# CLONE_EEPROM_95040_GMC_2A.net
KiCad netlist of a schematic drawn in EAGLE
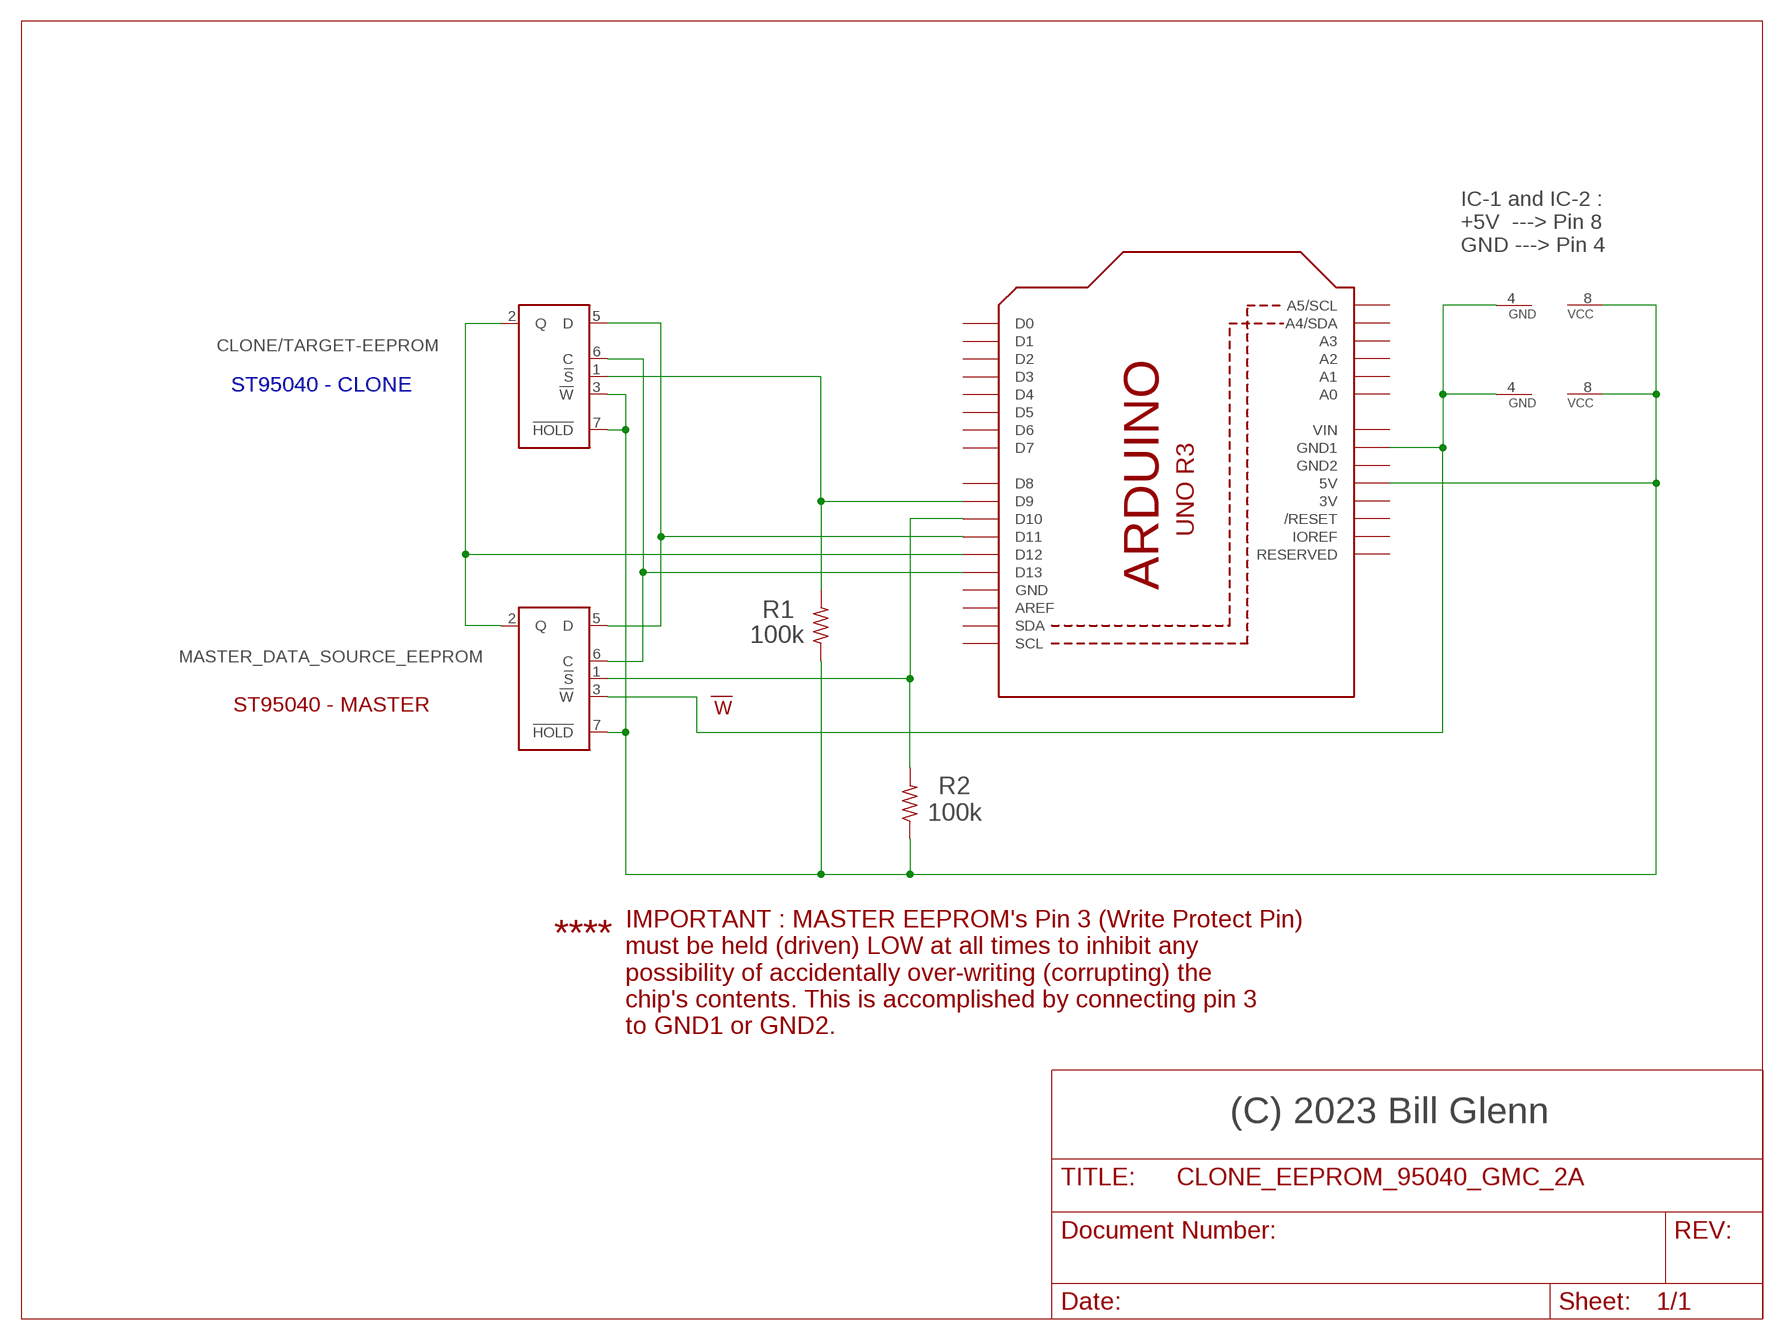
[diagram p0: schematic, sheet 1]

(export (version "E")
  (design (tool "Eeschema 10.0.6"))
  (components
    (comp (ref "CLONE/TARGET-EEPROM")
      (value "ST95040 - CLONE")
      (footprint "eagle-import:DIL-08")
      (libsource (lib "eagle-import") (part "ST95P08B"))
    )
    (comp (ref "MASTER_DATA_SOURCE_EEPROM")
      (value "ST95040 - MASTER")
      (footprint "eagle-import:DIL-08")
      (libsource (lib "eagle-import") (part "ST95P08B"))
    )
    (comp (ref "R1")
      (value "100k")
      (footprint "eagle-import:0207_15")
      (libsource (lib "eagle-import") (part "R-US_0207/15"))
    )
    (comp (ref "R2")
      (value "100k")
      (footprint "eagle-import:0207_15")
      (libsource (lib "eagle-import") (part "R-US_0207/15"))
    )
    (comp (ref "U1")
      (value "ARDUINOR3-BPLACE")
      (footprint "eagle-import:ARDUINOR3-BPLACE")
      (libsource (lib "eagle-import") (part "ARDUINOR3-BPLACE"))
    )
  )
  (nets
    (net (code "1") (name "/3V") (class "Default")
      (node (ref "U1") (pin "3V") (pinfunction "3V_3V") (pintype "power_in"))
    )
    (net (code "2") (name "/GND") (class "Default")
      (node (ref "U1") (pin "GND") (pinfunction "GND_GND") (pintype "power_in"))
    )
    (net (code "3") (name "/GND2") (class "Default")
      (node (ref "U1") (pin "GND2") (pinfunction "GND2_GND2") (pintype "power_in"))
    )
    (net (code "4") (name "/VIN") (class "Default")
      (node (ref "U1") (pin "VIN") (pinfunction "VIN_VIN") (pintype "power_in"))
    )
    (net (code "5") (name "Net-(CLONE/TARGET-EEPROMA-C)") (class "Default")
      (node (ref "CLONE/TARGET-EEPROM") (pin "6") (pinfunction "C_6") (pintype "input"))
      (node (ref "MASTER_DATA_SOURCE_EEPROM") (pin "6") (pinfunction "C_6") (pintype "input"))
      (node (ref "U1") (pin "D13") (pinfunction "D13_D13") (pintype "bidirectional"))
    )
    (net (code "6") (name "Net-(CLONE/TARGET-EEPROMA-D)") (class "Default")
      (node (ref "CLONE/TARGET-EEPROM") (pin "5") (pinfunction "D_5") (pintype "input"))
      (node (ref "MASTER_DATA_SOURCE_EEPROM") (pin "5") (pinfunction "D_5") (pintype "input"))
      (node (ref "U1") (pin "D11") (pinfunction "D11_D11") (pintype "bidirectional"))
    )
    (net (code "7") (name "Net-(CLONE/TARGET-EEPROMA-Q)") (class "Default")
      (node (ref "CLONE/TARGET-EEPROM") (pin "2") (pinfunction "Q_2") (pintype "tri_state"))
      (node (ref "MASTER_DATA_SOURCE_EEPROM") (pin "2") (pinfunction "Q_2") (pintype "tri_state"))
      (node (ref "U1") (pin "D12") (pinfunction "D12_D12") (pintype "bidirectional"))
    )
    (net (code "8") (name "Net-(CLONE/TARGET-EEPROMA-~{HOLD})") (class "Default")
      (node (ref "CLONE/TARGET-EEPROM") (pin "3") (pinfunction "~{W}_3") (pintype "input"))
      (node (ref "CLONE/TARGET-EEPROM") (pin "7") (pinfunction "~{HOLD}_7") (pintype "input"))
      (node (ref "CLONE/TARGET-EEPROM") (pin "8") (pinfunction "VCC_8") (pintype "power_in"))
      (node (ref "MASTER_DATA_SOURCE_EEPROM") (pin "7") (pinfunction "~{HOLD}_7") (pintype "input"))
      (node (ref "MASTER_DATA_SOURCE_EEPROM") (pin "8") (pinfunction "VCC_8") (pintype "power_in"))
      (node (ref "R1") (pin "1") (pinfunction "1_1") (pintype "passive"))
      (node (ref "R2") (pin "1") (pinfunction "1_1") (pintype "passive"))
      (node (ref "U1") (pin "5V") (pinfunction "5V_5V") (pintype "power_in"))
    )
    (net (code "9") (name "Net-(CLONE/TARGET-EEPROMA-~{S})") (class "Default")
      (node (ref "CLONE/TARGET-EEPROM") (pin "1") (pinfunction "~{S}_1") (pintype "input"))
      (node (ref "R1") (pin "2") (pinfunction "2_2") (pintype "passive"))
      (node (ref "U1") (pin "D9") (pinfunction "D9_D9") (pintype "bidirectional"))
    )
    (net (code "10") (name "Net-(CLONE/TARGET-EEPROMB-GND)") (class "Default")
      (node (ref "CLONE/TARGET-EEPROM") (pin "4") (pinfunction "GND_4") (pintype "power_in"))
      (node (ref "MASTER_DATA_SOURCE_EEPROM") (pin "3") (pinfunction "~{W}_3") (pintype "input"))
      (node (ref "MASTER_DATA_SOURCE_EEPROM") (pin "4") (pinfunction "GND_4") (pintype "power_in"))
      (node (ref "U1") (pin "GND1") (pinfunction "GND1_GND1") (pintype "power_in"))
    )
    (net (code "11") (name "Net-(MASTER_DATA_SOURCE_EEPROMA-~{S})") (class "Default")
      (node (ref "MASTER_DATA_SOURCE_EEPROM") (pin "1") (pinfunction "~{S}_1") (pintype "input"))
      (node (ref "R2") (pin "2") (pinfunction "2_2") (pintype "passive"))
      (node (ref "U1") (pin "D10") (pinfunction "D10_D10") (pintype "bidirectional"))
    )
    (net (code "12") (name "unconnected-(U1-A4{slash}SDA-PadA4)") (class "Default")
      (node (ref "U1") (pin "A4") (pinfunction "A4/SDA_A4") (pintype "bidirectional"))
    )
    (net (code "13") (name "unconnected-(U1-A5{slash}SCL-PadA5)") (class "Default")
      (node (ref "U1") (pin "A5") (pinfunction "A5/SCL_A5") (pintype "bidirectional"))
    )
    (net (code "14") (name "unconnected-(U1-PadA0)") (class "Default")
      (node (ref "U1") (pin "A0") (pinfunction "A0_A0") (pintype "bidirectional"))
    )
    (net (code "15") (name "unconnected-(U1-PadA1)") (class "Default")
      (node (ref "U1") (pin "A1") (pinfunction "A1_A1") (pintype "bidirectional"))
    )
    (net (code "16") (name "unconnected-(U1-PadA2)") (class "Default")
      (node (ref "U1") (pin "A2") (pinfunction "A2_A2") (pintype "bidirectional"))
    )
    (net (code "17") (name "unconnected-(U1-PadA3)") (class "Default")
      (node (ref "U1") (pin "A3") (pinfunction "A3_A3") (pintype "bidirectional"))
    )
    (net (code "18") (name "unconnected-(U1-PadAREF)") (class "Default")
      (node (ref "U1") (pin "AREF") (pinfunction "AREF_AREF") (pintype "bidirectional"))
    )
    (net (code "19") (name "unconnected-(U1-PadD0)") (class "Default")
      (node (ref "U1") (pin "D0") (pinfunction "D0_D0") (pintype "bidirectional"))
    )
    (net (code "20") (name "unconnected-(U1-PadD1)") (class "Default")
      (node (ref "U1") (pin "D1") (pinfunction "D1_D1") (pintype "bidirectional"))
    )
    (net (code "21") (name "unconnected-(U1-PadD2)") (class "Default")
      (node (ref "U1") (pin "D2") (pinfunction "D2_D2") (pintype "bidirectional"))
    )
    (net (code "22") (name "unconnected-(U1-PadD3)") (class "Default")
      (node (ref "U1") (pin "D3") (pinfunction "D3_D3") (pintype "bidirectional"))
    )
    (net (code "23") (name "unconnected-(U1-PadD4)") (class "Default")
      (node (ref "U1") (pin "D4") (pinfunction "D4_D4") (pintype "bidirectional"))
    )
    (net (code "24") (name "unconnected-(U1-PadD5)") (class "Default")
      (node (ref "U1") (pin "D5") (pinfunction "D5_D5") (pintype "bidirectional"))
    )
    (net (code "25") (name "unconnected-(U1-PadD6)") (class "Default")
      (node (ref "U1") (pin "D6") (pinfunction "D6_D6") (pintype "bidirectional"))
    )
    (net (code "26") (name "unconnected-(U1-PadD7)") (class "Default")
      (node (ref "U1") (pin "D7") (pinfunction "D7_D7") (pintype "bidirectional"))
    )
    (net (code "27") (name "unconnected-(U1-PadD8)") (class "Default")
      (node (ref "U1") (pin "D8") (pinfunction "D8_D8") (pintype "bidirectional"))
    )
    (net (code "28") (name "unconnected-(U1-PadIOREF)") (class "Default")
      (node (ref "U1") (pin "IOREF") (pinfunction "IOREF_IOREF") (pintype "output"))
    )
    (net (code "29") (name "unconnected-(U1-PadRESERVED)") (class "Default")
      (node (ref "U1") (pin "RESERVED") (pinfunction "RESERVED_RESERVED") (pintype "no_connect"))
    )
    (net (code "30") (name "unconnected-(U1-PadSCL)") (class "Default")
      (node (ref "U1") (pin "SCL") (pinfunction "SCL_SCL") (pintype "bidirectional"))
    )
    (net (code "31") (name "unconnected-(U1-PadSDA)") (class "Default")
      (node (ref "U1") (pin "SDA") (pinfunction "SDA_SDA") (pintype "bidirectional"))
    )
    (net (code "32") (name "unconnected-(U1-{slash}RESET-PadRESET)") (class "Default")
      (node (ref "U1") (pin "RESET") (pinfunction "/RESET_RESET") (pintype "bidirectional"))
    )
  )
)
